# master_before.net
KiCad netlist of a schematic drawn in EAGLE
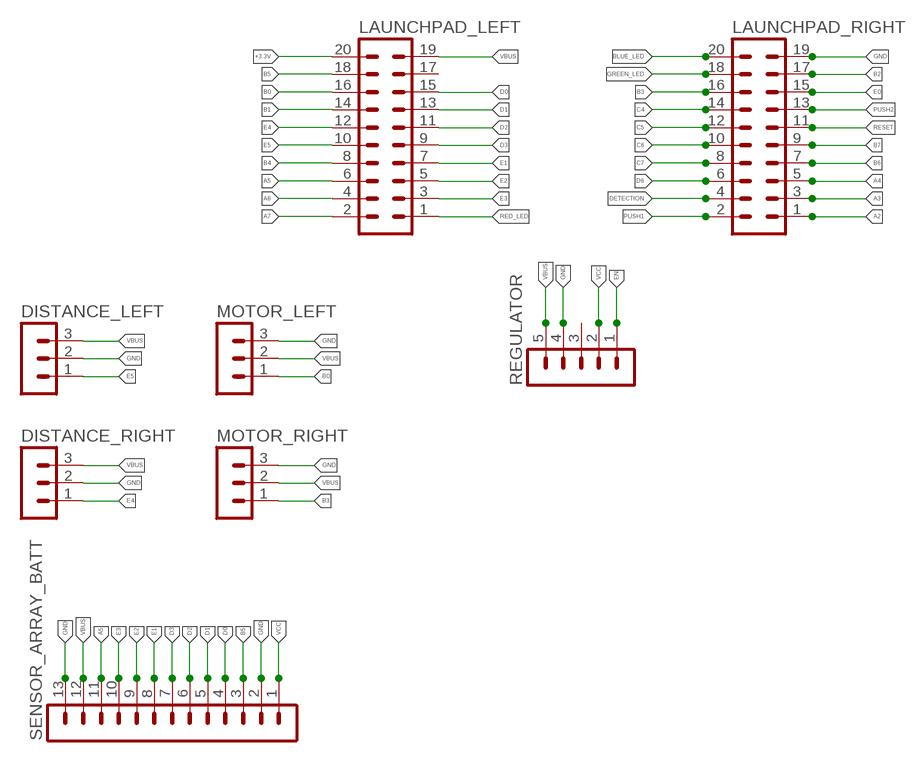
[diagram p0: schematic, sheet 1]

(export (version "E")
  (design (tool "Eeschema 10.0.6"))
  (components
    (comp (ref "DISTANCE_LEFT")
      (value "MA03-1")
      (footprint "eagle-import:MA03-1")
      (libsource (lib "eagle-import") (part "MA03-1"))
    )
    (comp (ref "DISTANCE_RIGHT")
      (value "MA03-1")
      (footprint "eagle-import:MA03-1")
      (libsource (lib "eagle-import") (part "MA03-1"))
    )
    (comp (ref "LAUNCHPAD_LEFT")
      (value "MA10-2")
      (footprint "eagle-import:MA10-2")
      (libsource (lib "eagle-import") (part "MA10-2"))
    )
    (comp (ref "LAUNCHPAD_RIGHT")
      (value "MA10-2")
      (footprint "eagle-import:MA10-2")
      (libsource (lib "eagle-import") (part "MA10-2"))
    )
    (comp (ref "MOTOR_LEFT")
      (value "MA03-1")
      (footprint "eagle-import:MA03-1")
      (libsource (lib "eagle-import") (part "MA03-1"))
    )
    (comp (ref "MOTOR_RIGHT")
      (value "MA03-1")
      (footprint "eagle-import:MA03-1")
      (libsource (lib "eagle-import") (part "MA03-1"))
    )
    (comp (ref "REGULATOR")
      (value "MA05-1")
      (footprint "eagle-import:MA05-1")
      (libsource (lib "eagle-import") (part "MA05-1"))
    )
    (comp (ref "SENSOR_ARRAY_BATT")
      (value "MA13-1")
      (footprint "eagle-import:MA13-1")
      (fields (field (name "SPICEPREFIX") "X"))
      (libsource (lib "eagle-import") (part "MA13-1"))
    )
  )
  (nets
    (net (code "1") (name "+3.3V") (class "Default")
      (node (ref "LAUNCHPAD_LEFT") (pin "20") (pinfunction "20_20") (pintype "passive"))
    )
    (net (code "2") (name "A2") (class "Default")
      (node (ref "LAUNCHPAD_RIGHT") (pin "1") (pinfunction "1_1") (pintype "passive"))
    )
    (net (code "3") (name "A3") (class "Default")
      (node (ref "LAUNCHPAD_RIGHT") (pin "3") (pinfunction "3_3") (pintype "passive"))
    )
    (net (code "4") (name "A4") (class "Default")
      (node (ref "LAUNCHPAD_RIGHT") (pin "5") (pinfunction "5_5") (pintype "passive"))
    )
    (net (code "5") (name "A5") (class "Default")
      (node (ref "LAUNCHPAD_LEFT") (pin "6") (pinfunction "6_6") (pintype "passive"))
      (node (ref "SENSOR_ARRAY_BATT") (pin "11") (pinfunction "11_11") (pintype "passive"))
    )
    (net (code "6") (name "A6") (class "Default")
      (node (ref "LAUNCHPAD_LEFT") (pin "4") (pinfunction "4_4") (pintype "passive"))
    )
    (net (code "7") (name "A7") (class "Default")
      (node (ref "LAUNCHPAD_LEFT") (pin "2") (pinfunction "2_2") (pintype "passive"))
    )
    (net (code "8") (name "B0") (class "Default")
      (node (ref "LAUNCHPAD_LEFT") (pin "16") (pinfunction "16_16") (pintype "passive"))
      (node (ref "MOTOR_LEFT") (pin "1") (pinfunction "1_1") (pintype "passive"))
    )
    (net (code "9") (name "B1") (class "Default")
      (node (ref "LAUNCHPAD_LEFT") (pin "14") (pinfunction "14_14") (pintype "passive"))
    )
    (net (code "10") (name "B2") (class "Default")
      (node (ref "LAUNCHPAD_RIGHT") (pin "17") (pinfunction "17_17") (pintype "passive"))
    )
    (net (code "11") (name "B3") (class "Default")
      (node (ref "LAUNCHPAD_RIGHT") (pin "16") (pinfunction "16_16") (pintype "passive"))
      (node (ref "MOTOR_RIGHT") (pin "1") (pinfunction "1_1") (pintype "passive"))
    )
    (net (code "12") (name "B4") (class "Default")
      (node (ref "LAUNCHPAD_LEFT") (pin "8") (pinfunction "8_8") (pintype "passive"))
    )
    (net (code "13") (name "B5") (class "Default")
      (node (ref "LAUNCHPAD_LEFT") (pin "18") (pinfunction "18_18") (pintype "passive"))
      (node (ref "SENSOR_ARRAY_BATT") (pin "3") (pinfunction "3_3") (pintype "passive"))
    )
    (net (code "14") (name "B6") (class "Default")
      (node (ref "LAUNCHPAD_RIGHT") (pin "7") (pinfunction "7_7") (pintype "passive"))
    )
    (net (code "15") (name "B7") (class "Default")
      (node (ref "LAUNCHPAD_RIGHT") (pin "9") (pinfunction "9_9") (pintype "passive"))
    )
    (net (code "16") (name "BLUE_LED") (class "Default")
      (node (ref "LAUNCHPAD_RIGHT") (pin "20") (pinfunction "20_20") (pintype "passive"))
    )
    (net (code "17") (name "C4") (class "Default")
      (node (ref "LAUNCHPAD_RIGHT") (pin "14") (pinfunction "14_14") (pintype "passive"))
    )
    (net (code "18") (name "C5") (class "Default")
      (node (ref "LAUNCHPAD_RIGHT") (pin "12") (pinfunction "12_12") (pintype "passive"))
    )
    (net (code "19") (name "C6") (class "Default")
      (node (ref "LAUNCHPAD_RIGHT") (pin "10") (pinfunction "10_10") (pintype "passive"))
    )
    (net (code "20") (name "C7") (class "Default")
      (node (ref "LAUNCHPAD_RIGHT") (pin "8") (pinfunction "8_8") (pintype "passive"))
    )
    (net (code "21") (name "D0") (class "Default")
      (node (ref "LAUNCHPAD_LEFT") (pin "15") (pinfunction "15_15") (pintype "passive"))
      (node (ref "SENSOR_ARRAY_BATT") (pin "4") (pinfunction "4_4") (pintype "passive"))
    )
    (net (code "22") (name "D1") (class "Default")
      (node (ref "LAUNCHPAD_LEFT") (pin "13") (pinfunction "13_13") (pintype "passive"))
      (node (ref "SENSOR_ARRAY_BATT") (pin "5") (pinfunction "5_5") (pintype "passive"))
    )
    (net (code "23") (name "D2") (class "Default")
      (node (ref "LAUNCHPAD_LEFT") (pin "11") (pinfunction "11_11") (pintype "passive"))
      (node (ref "SENSOR_ARRAY_BATT") (pin "6") (pinfunction "6_6") (pintype "passive"))
    )
    (net (code "24") (name "D3") (class "Default")
      (node (ref "LAUNCHPAD_LEFT") (pin "9") (pinfunction "9_9") (pintype "passive"))
      (node (ref "SENSOR_ARRAY_BATT") (pin "7") (pinfunction "7_7") (pintype "passive"))
    )
    (net (code "25") (name "D6") (class "Default")
      (node (ref "LAUNCHPAD_RIGHT") (pin "6") (pinfunction "6_6") (pintype "passive"))
    )
    (net (code "26") (name "DETECTION") (class "Default")
      (node (ref "LAUNCHPAD_RIGHT") (pin "4") (pinfunction "4_4") (pintype "passive"))
    )
    (net (code "27") (name "E0") (class "Default")
      (node (ref "LAUNCHPAD_RIGHT") (pin "15") (pinfunction "15_15") (pintype "passive"))
    )
    (net (code "28") (name "E1") (class "Default")
      (node (ref "LAUNCHPAD_LEFT") (pin "7") (pinfunction "7_7") (pintype "passive"))
      (node (ref "SENSOR_ARRAY_BATT") (pin "8") (pinfunction "8_8") (pintype "passive"))
    )
    (net (code "29") (name "E2") (class "Default")
      (node (ref "LAUNCHPAD_LEFT") (pin "5") (pinfunction "5_5") (pintype "passive"))
      (node (ref "SENSOR_ARRAY_BATT") (pin "9") (pinfunction "9_9") (pintype "passive"))
    )
    (net (code "30") (name "E3") (class "Default")
      (node (ref "LAUNCHPAD_LEFT") (pin "3") (pinfunction "3_3") (pintype "passive"))
      (node (ref "SENSOR_ARRAY_BATT") (pin "10") (pinfunction "10_10") (pintype "passive"))
    )
    (net (code "31") (name "E4") (class "Default")
      (node (ref "DISTANCE_RIGHT") (pin "1") (pinfunction "1_1") (pintype "passive"))
      (node (ref "LAUNCHPAD_LEFT") (pin "12") (pinfunction "12_12") (pintype "passive"))
    )
    (net (code "32") (name "E5") (class "Default")
      (node (ref "DISTANCE_LEFT") (pin "1") (pinfunction "1_1") (pintype "passive"))
      (node (ref "LAUNCHPAD_LEFT") (pin "10") (pinfunction "10_10") (pintype "passive"))
    )
    (net (code "33") (name "EN") (class "Default")
      (node (ref "REGULATOR") (pin "1") (pinfunction "1_1") (pintype "passive"))
    )
    (net (code "34") (name "GND") (class "Default")
      (node (ref "DISTANCE_LEFT") (pin "2") (pinfunction "2_2") (pintype "passive"))
      (node (ref "DISTANCE_RIGHT") (pin "2") (pinfunction "2_2") (pintype "passive"))
      (node (ref "LAUNCHPAD_RIGHT") (pin "19") (pinfunction "19_19") (pintype "passive"))
      (node (ref "MOTOR_LEFT") (pin "3") (pinfunction "3_3") (pintype "passive"))
      (node (ref "MOTOR_RIGHT") (pin "3") (pinfunction "3_3") (pintype "passive"))
      (node (ref "REGULATOR") (pin "4") (pinfunction "4_4") (pintype "passive"))
      (node (ref "SENSOR_ARRAY_BATT") (pin "13") (pinfunction "13_13") (pintype "passive"))
      (node (ref "SENSOR_ARRAY_BATT") (pin "2") (pinfunction "2_2") (pintype "passive"))
    )
    (net (code "35") (name "GREEN_LED") (class "Default")
      (node (ref "LAUNCHPAD_RIGHT") (pin "18") (pinfunction "18_18") (pintype "passive"))
    )
    (net (code "36") (name "PUSH1") (class "Default")
      (node (ref "LAUNCHPAD_RIGHT") (pin "2") (pinfunction "2_2") (pintype "passive"))
    )
    (net (code "37") (name "PUSH2") (class "Default")
      (node (ref "LAUNCHPAD_RIGHT") (pin "13") (pinfunction "13_13") (pintype "passive"))
    )
    (net (code "38") (name "RED_LED") (class "Default")
      (node (ref "LAUNCHPAD_LEFT") (pin "1") (pinfunction "1_1") (pintype "passive"))
    )
    (net (code "39") (name "RESET") (class "Default")
      (node (ref "LAUNCHPAD_RIGHT") (pin "11") (pinfunction "11_11") (pintype "passive"))
    )
    (net (code "40") (name "VBUS") (class "Default")
      (node (ref "DISTANCE_LEFT") (pin "3") (pinfunction "3_3") (pintype "passive"))
      (node (ref "DISTANCE_RIGHT") (pin "3") (pinfunction "3_3") (pintype "passive"))
      (node (ref "LAUNCHPAD_LEFT") (pin "19") (pinfunction "19_19") (pintype "passive"))
      (node (ref "MOTOR_LEFT") (pin "2") (pinfunction "2_2") (pintype "passive"))
      (node (ref "MOTOR_RIGHT") (pin "2") (pinfunction "2_2") (pintype "passive"))
      (node (ref "REGULATOR") (pin "5") (pinfunction "5_5") (pintype "passive"))
      (node (ref "SENSOR_ARRAY_BATT") (pin "12") (pinfunction "12_12") (pintype "passive"))
    )
    (net (code "41") (name "VCC") (class "Default")
      (node (ref "REGULATOR") (pin "2") (pinfunction "2_2") (pintype "passive"))
      (node (ref "SENSOR_ARRAY_BATT") (pin "1") (pinfunction "1_1") (pintype "passive"))
    )
    (net (code "42") (name "unconnected-(LAUNCHPAD_LEFT-Pad17)") (class "Default")
      (node (ref "LAUNCHPAD_LEFT") (pin "17") (pinfunction "17_17") (pintype "passive"))
    )
    (net (code "43") (name "unconnected-(REGULATOR-Pad3)") (class "Default")
      (node (ref "REGULATOR") (pin "3") (pinfunction "3_3") (pintype "passive"))
    )
  )
)
